# 780-00012-P3_rev3_Sch_M2_Focus_Drive.net
KiCad netlist of a schematic drawn in Altium Designer
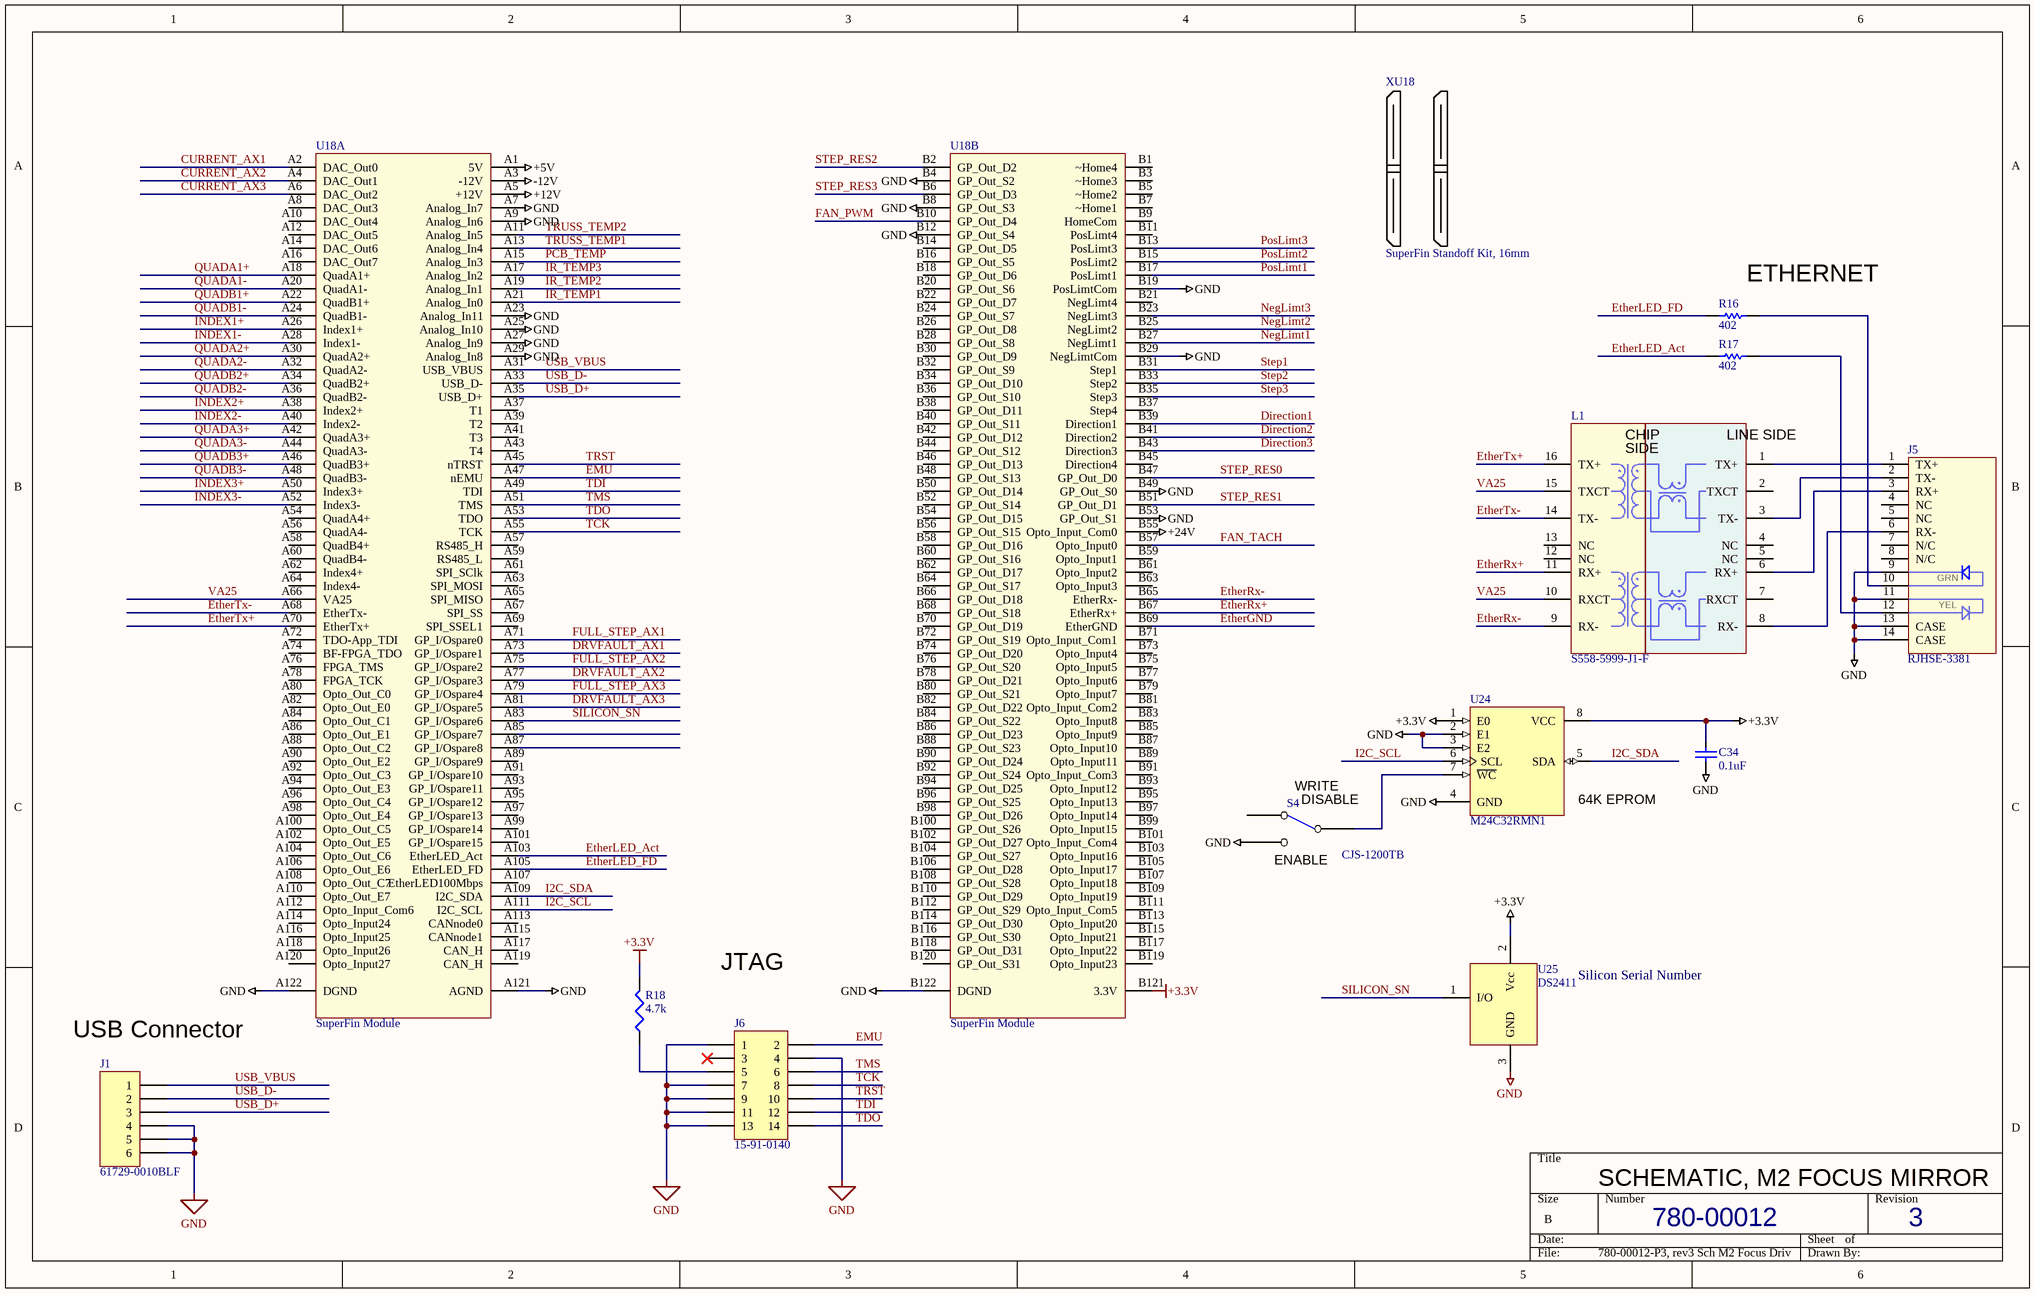
[diagram p0: 780-00012-P3, rev3 Sch M2 Focus Drive.SchDoc]

(export (version "E")
  (design (tool "Eeschema 10.0.6"))
  (components
    (comp (ref "C34")
      (value "0.1uF")
      (footprint "SMD_0805")
      (description "Capacitor")
      (fields (field (name "MANUFACTURER") "AVX") (field (name "Comment") "Cap SMD"))
      (libsource (lib "Richs Schematic Components") (part "Cap SMD"))
    )
    (comp (ref "J1")
      (value "61729-0010BLF")
      (footprint "USB Vertical PCB")
      (description "Header, 6-Pin")
      (fields (field (name "MANUFACTURER") "FCI"))
      (libsource (lib "Miscellaneous Connectors") (part "Header 6"))
    )
    (comp (ref "J5")
      (value "RJHSE-3381")
      (footprint "RJ45, VERT MOUNT, NO MAGNETICS")
      (description "Vertical PC mount, w/o magnetics")
      (libsource (lib "Richs Schematic Components") (part "CONN RJ-45 w/o magnetics"))
    )
    (comp (ref "J6")
      (value "15-91-0140")
      (footprint "HDR2X7")
      (description "Header, 7-Pin, Dual row")
      (fields (field (name "MANUFACTURER") "Molex/Waldom"))
      (libsource (lib "Miscellaneous Connectors") (part "Header 7X2"))
    )
    (comp (ref "L1")
      (value "S558-5999-J1-F")
      (footprint "10/100BT Magetics module")
      (description "10/100BT Magnetics Module")
      (libsource (lib "Richs Schematic Components") (part "Ethernet Magnetics module"))
    )
    (comp (ref "R16")
      (value "402")
      (footprint "SMD_0805")
      (description "Resistor 0805")
      (fields (field (name "MANUFACTURER") "Vishay/Dale") (field (name "Comment") "Res 0805"))
      (libsource (lib "Richs Schematic Components") (part "Res SMD"))
    )
    (comp (ref "R17")
      (value "402")
      (footprint "SMD_0805")
      (description "Resistor 0805")
      (fields (field (name "MANUFACTURER") "Vishay/Dale") (field (name "Comment") "Res 0805"))
      (libsource (lib "Richs Schematic Components") (part "Res SMD"))
    )
    (comp (ref "R18")
      (value "4.7k")
      (footprint "2012[0805]")
      (description "Resistor")
      (fields (field (name "MANUFACTURER") "Dale/Vishay"))
      (libsource (lib "Miscellaneous Devices") (part "Res3"))
    )
    (comp (ref "S4")
      (value "CJS-1200TB")
      (footprint "CAS-120B")
      (fields (field (name "MANUFACTURER") "Copal Electronics"))
      (libsource (lib "JON_1_Library") (part "SW_SPDT_DOUG"))
    )
    (comp (ref "U18")
      (value "SuperFin Module")
      (footprint "SuperFin Footprint")
      (libsource (lib "Richs Schematic Components") (part "SuperFin Module"))
    )
    (comp (ref "U24")
      (value "M24C32RMN1")
      (footprint "SOP8_N")
      (description "32 Kbit Serial I²C Bus EEPROM")
      (libsource (lib "ST Memory EEPROM Serial") (part "M24C32RMN1"))
    )
    (comp (ref "U25")
      (value "DS2411")
      (footprint "SMD_SOT23_3")
      (description "Silicon Serial Number")
      (fields (field (name "MANUFACTURER") "MAXIM"))
      (libsource (lib "Richs Schematic Components") (part "DS2411"))
    )
    (comp (ref "XU18")
      (value "SuperFin Standoff Kit, 16mm")
      (libsource (lib "Richs Schematic Components") (part "SuperFin Standoff Kit, 16mm"))
    )
  )
  (nets
    (net (code "1") (name "+3.3V") (class "Default")
      (node (ref "C34") (pin "2") (pinfunction "2_2") (pintype "passive"))
      (node (ref "R18") (pin "2") (pinfunction "2_2") (pintype "passive"))
      (node (ref "U18") (pin "B121") (pinfunction "3.3V_B121") (pintype "passive"))
      (node (ref "U24") (pin "1") (pinfunction "E0_1") (pintype "input"))
      (node (ref "U24") (pin "8") (pinfunction "VCC_8") (pintype "power_in"))
      (node (ref "U25") (pin "2") (pinfunction "Vcc_2") (pintype "passive"))
    )
    (net (code "2") (name "+5V") (class "Default")
      (node (ref "U18") (pin "A1") (pinfunction "5V_A1") (pintype "passive"))
    )
    (net (code "3") (name "+12V") (class "Default")
      (node (ref "U18") (pin "A5") (pinfunction "+12V_A5") (pintype "passive"))
    )
    (net (code "4") (name "+24V") (class "Default")
      (node (ref "U18") (pin "B55") (pinfunction "Opto_Input_Com0_B55") (pintype "passive"))
    )
    (net (code "5") (name "-12V") (class "Default")
      (node (ref "U18") (pin "A3") (pinfunction "-12V_A3") (pintype "passive"))
    )
    (net (code "6") (name "/CURRENT_AX1") (class "Default")
      (node (ref "U18") (pin "A2") (pinfunction "DAC_Out0_A2") (pintype "passive"))
    )
    (net (code "7") (name "/CURRENT_AX2") (class "Default")
      (node (ref "U18") (pin "A4") (pinfunction "DAC_Out1_A4") (pintype "passive"))
    )
    (net (code "8") (name "/CURRENT_AX3") (class "Default")
      (node (ref "U18") (pin "A6") (pinfunction "DAC_Out2_A6") (pintype "passive"))
    )
    (net (code "9") (name "/DRVFAULT_AX1") (class "Default")
      (node (ref "U18") (pin "A73") (pinfunction "GP_I/Ospare1_A73") (pintype "passive"))
    )
    (net (code "10") (name "/DRVFAULT_AX2") (class "Default")
      (node (ref "U18") (pin "A77") (pinfunction "GP_I/Ospare3_A77") (pintype "passive"))
    )
    (net (code "11") (name "/DRVFAULT_AX3") (class "Default")
      (node (ref "U18") (pin "A81") (pinfunction "GP_I/Ospare5_A81") (pintype "passive"))
    )
    (net (code "12") (name "/Direction1") (class "Default")
      (node (ref "U18") (pin "B39") (pinfunction "Direction1_B39") (pintype "passive"))
    )
    (net (code "13") (name "/Direction2") (class "Default")
      (node (ref "U18") (pin "B41") (pinfunction "Direction2_B41") (pintype "passive"))
    )
    (net (code "14") (name "/Direction3") (class "Default")
      (node (ref "U18") (pin "B43") (pinfunction "Direction3_B43") (pintype "passive"))
    )
    (net (code "15") (name "/EMU") (class "Default")
      (node (ref "J6") (pin "2") (pinfunction "2_2") (pintype "passive"))
      (node (ref "U18") (pin "A47") (pinfunction "nEMU_A47") (pintype "passive"))
    )
    (net (code "16") (name "/EtherGND") (class "Default")
      (node (ref "U18") (pin "B69") (pinfunction "EtherGND_B69") (pintype "passive"))
    )
    (net (code "17") (name "/EtherLED_Act") (class "Default")
      (node (ref "R17") (pin "1") (pinfunction "1_1") (pintype "passive"))
      (node (ref "U18") (pin "A103") (pinfunction "EtherLED_Act_A103") (pintype "passive"))
    )
    (net (code "18") (name "/EtherLED_FD") (class "Default")
      (node (ref "R16") (pin "1") (pinfunction "1_1") (pintype "passive"))
      (node (ref "U18") (pin "A105") (pinfunction "EtherLED_FD_A105") (pintype "passive"))
    )
    (net (code "19") (name "/EtherRx+") (class "Default")
      (node (ref "L1") (pin "11") (pinfunction "RX+_11") (pintype "passive"))
      (node (ref "U18") (pin "B67") (pinfunction "EtherRx+_B67") (pintype "passive"))
    )
    (net (code "20") (name "/EtherRx-") (class "Default")
      (node (ref "L1") (pin "9") (pinfunction "RX-_9") (pintype "passive"))
      (node (ref "U18") (pin "B65") (pinfunction "EtherRx-_B65") (pintype "passive"))
    )
    (net (code "21") (name "/EtherTx+") (class "Default")
      (node (ref "L1") (pin "16") (pinfunction "TX+_16") (pintype "passive"))
      (node (ref "U18") (pin "A70") (pinfunction "EtherTx+_A70") (pintype "passive"))
    )
    (net (code "22") (name "/EtherTx-") (class "Default")
      (node (ref "L1") (pin "14") (pinfunction "TX-_14") (pintype "passive"))
      (node (ref "U18") (pin "A68") (pinfunction "EtherTx-_A68") (pintype "passive"))
    )
    (net (code "23") (name "/FAN_PWM") (class "Default")
      (node (ref "U18") (pin "B10") (pinfunction "GP_Out_D4_B10") (pintype "passive"))
    )
    (net (code "24") (name "/FAN_TACH") (class "Default")
      (node (ref "U18") (pin "B57") (pinfunction "Opto_Input0_B57") (pintype "passive"))
    )
    (net (code "25") (name "/FULL_STEP_AX1") (class "Default")
      (node (ref "U18") (pin "A71") (pinfunction "GP_I/Ospare0_A71") (pintype "passive"))
    )
    (net (code "26") (name "/FULL_STEP_AX2") (class "Default")
      (node (ref "U18") (pin "A75") (pinfunction "GP_I/Ospare2_A75") (pintype "passive"))
    )
    (net (code "27") (name "/FULL_STEP_AX3") (class "Default")
      (node (ref "U18") (pin "A79") (pinfunction "GP_I/Ospare4_A79") (pintype "passive"))
    )
    (net (code "28") (name "/I2C_SCL") (class "Default")
      (node (ref "U18") (pin "A111") (pinfunction "I2C_SCL_A111") (pintype "passive"))
      (node (ref "U24") (pin "6") (pinfunction "SCL_6") (pintype "input"))
    )
    (net (code "29") (name "/I2C_SDA") (class "Default")
      (node (ref "U18") (pin "A109") (pinfunction "I2C_SDA_A109") (pintype "passive"))
      (node (ref "U24") (pin "5") (pinfunction "SDA_5") (pintype "bidirectional"))
    )
    (net (code "30") (name "/INDEX1+") (class "Default")
      (node (ref "U18") (pin "A26") (pinfunction "Index1+_A26") (pintype "passive"))
    )
    (net (code "31") (name "/INDEX1-") (class "Default")
      (node (ref "U18") (pin "A28") (pinfunction "Index1-_A28") (pintype "passive"))
    )
    (net (code "32") (name "/INDEX2+") (class "Default")
      (node (ref "U18") (pin "A38") (pinfunction "Index2+_A38") (pintype "passive"))
    )
    (net (code "33") (name "/INDEX2-") (class "Default")
      (node (ref "U18") (pin "A40") (pinfunction "Index2-_A40") (pintype "passive"))
    )
    (net (code "34") (name "/INDEX3+") (class "Default")
      (node (ref "U18") (pin "A50") (pinfunction "Index3+_A50") (pintype "passive"))
    )
    (net (code "35") (name "/INDEX3-") (class "Default")
      (node (ref "U18") (pin "A52") (pinfunction "Index3-_A52") (pintype "passive"))
    )
    (net (code "36") (name "/IR_TEMP1") (class "Default")
      (node (ref "U18") (pin "A21") (pinfunction "Analog_In0_A21") (pintype "passive"))
    )
    (net (code "37") (name "/IR_TEMP2") (class "Default")
      (node (ref "U18") (pin "A19") (pinfunction "Analog_In1_A19") (pintype "passive"))
    )
    (net (code "38") (name "/IR_TEMP3") (class "Default")
      (node (ref "U18") (pin "A17") (pinfunction "Analog_In2_A17") (pintype "passive"))
    )
    (net (code "39") (name "/NegLimt1") (class "Default")
      (node (ref "U18") (pin "B27") (pinfunction "NegLimt1_B27") (pintype "passive"))
    )
    (net (code "40") (name "/NegLimt2") (class "Default")
      (node (ref "U18") (pin "B25") (pinfunction "NegLimt2_B25") (pintype "passive"))
    )
    (net (code "41") (name "/NegLimt3") (class "Default")
      (node (ref "U18") (pin "B23") (pinfunction "NegLimt3_B23") (pintype "passive"))
    )
    (net (code "42") (name "/PCB_TEMP") (class "Default")
      (node (ref "U18") (pin "A15") (pinfunction "Analog_In3_A15") (pintype "passive"))
    )
    (net (code "43") (name "/PosLimt1") (class "Default")
      (node (ref "U18") (pin "B17") (pinfunction "PosLimt1_B17") (pintype "passive"))
    )
    (net (code "44") (name "/PosLimt2") (class "Default")
      (node (ref "U18") (pin "B15") (pinfunction "PosLimt2_B15") (pintype "passive"))
    )
    (net (code "45") (name "/PosLimt3") (class "Default")
      (node (ref "U18") (pin "B13") (pinfunction "PosLimt3_B13") (pintype "passive"))
    )
    (net (code "46") (name "/QUADA1+") (class "Default")
      (node (ref "U18") (pin "A18") (pinfunction "QuadA1+_A18") (pintype "passive"))
    )
    (net (code "47") (name "/QUADA1-") (class "Default")
      (node (ref "U18") (pin "A20") (pinfunction "QuadA1-_A20") (pintype "passive"))
    )
    (net (code "48") (name "/QUADA2+") (class "Default")
      (node (ref "U18") (pin "A30") (pinfunction "QuadA2+_A30") (pintype "passive"))
    )
    (net (code "49") (name "/QUADA2-") (class "Default")
      (node (ref "U18") (pin "A32") (pinfunction "QuadA2-_A32") (pintype "passive"))
    )
    (net (code "50") (name "/QUADA3+") (class "Default")
      (node (ref "U18") (pin "A42") (pinfunction "QuadA3+_A42") (pintype "passive"))
    )
    (net (code "51") (name "/QUADA3-") (class "Default")
      (node (ref "U18") (pin "A44") (pinfunction "QuadA3-_A44") (pintype "passive"))
    )
    (net (code "52") (name "/QUADB1+") (class "Default")
      (node (ref "U18") (pin "A22") (pinfunction "QuadB1+_A22") (pintype "passive"))
    )
    (net (code "53") (name "/QUADB1-") (class "Default")
      (node (ref "U18") (pin "A24") (pinfunction "QuadB1-_A24") (pintype "passive"))
    )
    (net (code "54") (name "/QUADB2+") (class "Default")
      (node (ref "U18") (pin "A34") (pinfunction "QuadB2+_A34") (pintype "passive"))
    )
    (net (code "55") (name "/QUADB2-") (class "Default")
      (node (ref "U18") (pin "A36") (pinfunction "QuadB2-_A36") (pintype "passive"))
    )
    (net (code "56") (name "/QUADB3+") (class "Default")
      (node (ref "U18") (pin "A46") (pinfunction "QuadB3+_A46") (pintype "passive"))
    )
    (net (code "57") (name "/QUADB3-") (class "Default")
      (node (ref "U18") (pin "A48") (pinfunction "QuadB3-_A48") (pintype "passive"))
    )
    (net (code "58") (name "/SILICON_SN") (class "Default")
      (node (ref "U18") (pin "A83") (pinfunction "GP_I/Ospare6_A83") (pintype "passive"))
      (node (ref "U25") (pin "1") (pinfunction "I/O_1") (pintype "passive"))
    )
    (net (code "59") (name "/STEP_RES0") (class "Default")
      (node (ref "U18") (pin "B47") (pinfunction "GP_Out_D0_B47") (pintype "passive"))
    )
    (net (code "60") (name "/STEP_RES1") (class "Default")
      (node (ref "U18") (pin "B51") (pinfunction "GP_Out_D1_B51") (pintype "passive"))
    )
    (net (code "61") (name "/STEP_RES2") (class "Default")
      (node (ref "U18") (pin "B2") (pinfunction "GP_Out_D2_B2") (pintype "passive"))
    )
    (net (code "62") (name "/STEP_RES3") (class "Default")
      (node (ref "U18") (pin "B6") (pinfunction "GP_Out_D3_B6") (pintype "passive"))
    )
    (net (code "63") (name "/Step1") (class "Default")
      (node (ref "U18") (pin "B31") (pinfunction "Step1_B31") (pintype "passive"))
    )
    (net (code "64") (name "/Step2") (class "Default")
      (node (ref "U18") (pin "B33") (pinfunction "Step2_B33") (pintype "passive"))
    )
    (net (code "65") (name "/Step3") (class "Default")
      (node (ref "U18") (pin "B35") (pinfunction "Step3_B35") (pintype "passive"))
    )
    (net (code "66") (name "/TCK") (class "Default")
      (node (ref "J6") (pin "8") (pinfunction "8_8") (pintype "passive"))
      (node (ref "U18") (pin "A55") (pinfunction "TCK_A55") (pintype "passive"))
    )
    (net (code "67") (name "/TDI") (class "Default")
      (node (ref "J6") (pin "12") (pinfunction "12_12") (pintype "passive"))
      (node (ref "U18") (pin "A49") (pinfunction "TDI_A49") (pintype "passive"))
    )
    (net (code "68") (name "/TDO") (class "Default")
      (node (ref "J6") (pin "14") (pinfunction "14_14") (pintype "passive"))
      (node (ref "U18") (pin "A53") (pinfunction "TDO_A53") (pintype "passive"))
    )
    (net (code "69") (name "/TMS") (class "Default")
      (node (ref "J6") (pin "6") (pinfunction "6_6") (pintype "passive"))
      (node (ref "U18") (pin "A51") (pinfunction "TMS_A51") (pintype "passive"))
    )
    (net (code "70") (name "/TRST") (class "Default")
      (node (ref "J6") (pin "10") (pinfunction "10_10") (pintype "passive"))
      (node (ref "U18") (pin "A45") (pinfunction "nTRST_A45") (pintype "passive"))
    )
    (net (code "71") (name "/TRUSS_TEMP1") (class "Default")
      (node (ref "U18") (pin "A13") (pinfunction "Analog_In4_A13") (pintype "passive"))
    )
    (net (code "72") (name "/TRUSS_TEMP2") (class "Default")
      (node (ref "U18") (pin "A11") (pinfunction "Analog_In5_A11") (pintype "passive"))
    )
    (net (code "73") (name "/USB_D+") (class "Default")
      (node (ref "J1") (pin "3") (pinfunction "3_3") (pintype "passive"))
      (node (ref "U18") (pin "A35") (pinfunction "USB_D+_A35") (pintype "passive"))
    )
    (net (code "74") (name "/USB_D-") (class "Default")
      (node (ref "J1") (pin "2") (pinfunction "2_2") (pintype "passive"))
      (node (ref "U18") (pin "A33") (pinfunction "USB_D-_A33") (pintype "passive"))
    )
    (net (code "75") (name "/USB_VBUS") (class "Default")
      (node (ref "J1") (pin "1") (pinfunction "1_1") (pintype "passive"))
      (node (ref "U18") (pin "A31") (pinfunction "USB_VBUS_A31") (pintype "passive"))
    )
    (net (code "76") (name "/VA25") (class "Default")
      (node (ref "L1") (pin "10") (pinfunction "RXCT_10") (pintype "passive"))
      (node (ref "L1") (pin "15") (pinfunction "TXCT_15") (pintype "passive"))
      (node (ref "U18") (pin "A66") (pinfunction "VA25_A66") (pintype "passive"))
    )
    (net (code "77") (name "GND") (class "Default")
      (node (ref "C34") (pin "1") (pinfunction "1_1") (pintype "passive"))
      (node (ref "J1") (pin "4") (pinfunction "4_4") (pintype "passive"))
      (node (ref "J1") (pin "5") (pinfunction "5_5") (pintype "passive"))
      (node (ref "J1") (pin "6") (pinfunction "6_6") (pintype "passive"))
      (node (ref "J5") (pin "11") (pinfunction "YEL-Cathode_11") (pintype "passive"))
      (node (ref "J5") (pin "13") (pinfunction "CASE_13") (pintype "passive"))
      (node (ref "J5") (pin "14") (pinfunction "CASE_14") (pintype "passive"))
      (node (ref "J5") (pin "9") (pinfunction "GRN-Anode_9") (pintype "passive"))
      (node (ref "J6") (pin "1") (pinfunction "1_1") (pintype "passive"))
      (node (ref "J6") (pin "11") (pinfunction "11_11") (pintype "passive"))
      (node (ref "J6") (pin "13") (pinfunction "13_13") (pintype "passive"))
      (node (ref "J6") (pin "4") (pinfunction "4_4") (pintype "passive"))
      (node (ref "J6") (pin "7") (pinfunction "7_7") (pintype "passive"))
      (node (ref "J6") (pin "9") (pinfunction "9_9") (pintype "passive"))
      (node (ref "S4") (pin "1") (pinfunction "NO_1") (pintype "passive"))
      (node (ref "U18") (pin "A121") (pinfunction "AGND_A121") (pintype "passive"))
      (node (ref "U18") (pin "A122") (pinfunction "DGND_A122") (pintype "passive"))
      (node (ref "U18") (pin "A23") (pinfunction "Analog_In11_A23") (pintype "passive"))
      (node (ref "U18") (pin "A25") (pinfunction "Analog_In10_A25") (pintype "passive"))
      (node (ref "U18") (pin "A27") (pinfunction "Analog_In9_A27") (pintype "passive"))
      (node (ref "U18") (pin "A29") (pinfunction "Analog_In8_A29") (pintype "passive"))
      (node (ref "U18") (pin "A7") (pinfunction "Analog_In7_A7") (pintype "passive"))
      (node (ref "U18") (pin "A9") (pinfunction "Analog_In6_A9") (pintype "passive"))
      (node (ref "U18") (pin "B12") (pinfunction "GP_Out_S4_B12") (pintype "passive"))
      (node (ref "U18") (pin "B122") (pinfunction "DGND_B122") (pintype "passive"))
      (node (ref "U18") (pin "B19") (pinfunction "PosLimtCom_B19") (pintype "passive"))
      (node (ref "U18") (pin "B29") (pinfunction "NegLimtCom_B29") (pintype "passive"))
      (node (ref "U18") (pin "B4") (pinfunction "GP_Out_S2_B4") (pintype "passive"))
      (node (ref "U18") (pin "B49") (pinfunction "GP_Out_S0_B49") (pintype "passive"))
      (node (ref "U18") (pin "B53") (pinfunction "GP_Out_S1_B53") (pintype "passive"))
      (node (ref "U18") (pin "B8") (pinfunction "GP_Out_S3_B8") (pintype "passive"))
      (node (ref "U24") (pin "2") (pinfunction "E1_2") (pintype "input"))
      (node (ref "U24") (pin "3") (pinfunction "E2_3") (pintype "input"))
      (node (ref "U24") (pin "4") (pinfunction "GND_4") (pintype "power_in"))
      (node (ref "U25") (pin "3") (pinfunction "GND_3") (pintype "passive"))
    )
    (net (code "78") (name "Net-(J5-GRN-Cathode)") (class "Default")
      (node (ref "J5") (pin "10") (pinfunction "GRN-Cathode_10") (pintype "passive"))
      (node (ref "R16") (pin "2") (pinfunction "2_2") (pintype "passive"))
    )
    (net (code "79") (name "Net-(J5-RX+)") (class "Default")
      (node (ref "J5") (pin "3") (pinfunction "RX+_3") (pintype "passive"))
      (node (ref "L1") (pin "6") (pinfunction "RX+_6") (pintype "passive"))
    )
    (net (code "80") (name "Net-(J5-RX-)") (class "Default")
      (node (ref "J5") (pin "6") (pinfunction "RX-_6") (pintype "passive"))
      (node (ref "L1") (pin "8") (pinfunction "RX-_8") (pintype "passive"))
    )
    (net (code "81") (name "Net-(J5-TX+)") (class "Default")
      (node (ref "J5") (pin "1") (pinfunction "TX+_1") (pintype "passive"))
      (node (ref "L1") (pin "1") (pinfunction "TX+_1") (pintype "passive"))
    )
    (net (code "82") (name "Net-(J5-TX-)") (class "Default")
      (node (ref "J5") (pin "2") (pinfunction "TX-_2") (pintype "passive"))
      (node (ref "L1") (pin "3") (pinfunction "TX-_3") (pintype "passive"))
    )
    (net (code "83") (name "Net-(J5-YEL-Anode)") (class "Default")
      (node (ref "J5") (pin "12") (pinfunction "YEL-Anode_12") (pintype "passive"))
      (node (ref "R17") (pin "2") (pinfunction "2_2") (pintype "passive"))
    )
    (net (code "84") (name "Net-(J6-Pad5)") (class "Default")
      (node (ref "J6") (pin "5") (pinfunction "5_5") (pintype "passive"))
      (node (ref "R18") (pin "1") (pinfunction "1_1") (pintype "passive"))
    )
    (net (code "85") (name "Net-(S4-COM)") (class "Default")
      (node (ref "S4") (pin "2") (pinfunction "COM_2") (pintype "passive"))
      (node (ref "U24") (pin "7") (pinfunction "~{WC}_7") (pintype "input"))
    )
    (net (code "86") (name "unconnected-(J5-NC-Pad4)") (class "Default")
      (node (ref "J5") (pin "4") (pinfunction "NC_4") (pintype "passive"))
    )
    (net (code "87") (name "unconnected-(J5-NC-Pad5)") (class "Default")
      (node (ref "J5") (pin "5") (pinfunction "NC_5") (pintype "passive"))
    )
    (net (code "88") (name "unconnected-(J5-N{slash}C-Pad7)") (class "Default")
      (node (ref "J5") (pin "7") (pinfunction "N/C_7") (pintype "passive"))
    )
    (net (code "89") (name "unconnected-(J5-N{slash}C-Pad8)") (class "Default")
      (node (ref "J5") (pin "8") (pinfunction "N/C_8") (pintype "passive"))
    )
    (net (code "90") (name "unconnected-(J6-Pad3)") (class "Default")
      (node (ref "J6") (pin "3") (pinfunction "3_3") (pintype "passive+no_connect"))
    )
    (net (code "91") (name "unconnected-(L1-NC-Pad4)") (class "Default")
      (node (ref "L1") (pin "4") (pinfunction "NC_4") (pintype "passive"))
    )
    (net (code "92") (name "unconnected-(L1-NC-Pad5)") (class "Default")
      (node (ref "L1") (pin "5") (pinfunction "NC_5") (pintype "passive"))
    )
    (net (code "93") (name "unconnected-(L1-NC-Pad12)") (class "Default")
      (node (ref "L1") (pin "12") (pinfunction "NC_12") (pintype "passive"))
    )
    (net (code "94") (name "unconnected-(L1-NC-Pad13)") (class "Default")
      (node (ref "L1") (pin "13") (pinfunction "NC_13") (pintype "passive"))
    )
    (net (code "95") (name "unconnected-(L1-RXCT-Pad7)") (class "Default")
      (node (ref "L1") (pin "7") (pinfunction "RXCT_7") (pintype "passive"))
    )
    (net (code "96") (name "unconnected-(L1-TXCT-Pad2)") (class "Default")
      (node (ref "L1") (pin "2") (pinfunction "TXCT_2") (pintype "passive"))
    )
    (net (code "97") (name "unconnected-(S4-NC-Pad3)") (class "Default")
      (node (ref "S4") (pin "3") (pinfunction "NC_3") (pintype "passive"))
    )
    (net (code "98") (name "unconnected-(U18A-BF-FPGA_TDO-PadA74)") (class "Default")
      (node (ref "U18") (pin "A74") (pinfunction "BF-FPGA_TDO_A74") (pintype "passive"))
    )
    (net (code "99") (name "unconnected-(U18A-CAN_H-PadA117)") (class "Default")
      (node (ref "U18") (pin "A117") (pinfunction "CAN_H_A117") (pintype "passive"))
    )
    (net (code "100") (name "unconnected-(U18A-CAN_H-PadA119)") (class "Default")
      (node (ref "U18") (pin "A119") (pinfunction "CAN_H_A119") (pintype "passive"))
    )
    (net (code "101") (name "unconnected-(U18A-CANnode0-PadA113)") (class "Default")
      (node (ref "U18") (pin "A113") (pinfunction "CANnode0_A113") (pintype "passive"))
    )
    (net (code "102") (name "unconnected-(U18A-CANnode1-PadA115)") (class "Default")
      (node (ref "U18") (pin "A115") (pinfunction "CANnode1_A115") (pintype "passive"))
    )
    (net (code "103") (name "unconnected-(U18A-DAC_Out3-PadA8)") (class "Default")
      (node (ref "U18") (pin "A8") (pinfunction "DAC_Out3_A8") (pintype "passive"))
    )
    (net (code "104") (name "unconnected-(U18A-DAC_Out4-PadA10)") (class "Default")
      (node (ref "U18") (pin "A10") (pinfunction "DAC_Out4_A10") (pintype "passive"))
    )
    (net (code "105") (name "unconnected-(U18A-DAC_Out5-PadA12)") (class "Default")
      (node (ref "U18") (pin "A12") (pinfunction "DAC_Out5_A12") (pintype "passive"))
    )
    (net (code "106") (name "unconnected-(U18A-DAC_Out6-PadA14)") (class "Default")
      (node (ref "U18") (pin "A14") (pinfunction "DAC_Out6_A14") (pintype "passive"))
    )
    (net (code "107") (name "unconnected-(U18A-DAC_Out7-PadA16)") (class "Default")
      (node (ref "U18") (pin "A16") (pinfunction "DAC_Out7_A16") (pintype "passive"))
    )
    (net (code "108") (name "unconnected-(U18A-EtherLED100Mbps-PadA107)") (class "Default")
      (node (ref "U18") (pin "A107") (pinfunction "EtherLED100Mbps_A107") (pintype "passive"))
    )
    (net (code "109") (name "unconnected-(U18A-FPGA_TCK-PadA78)") (class "Default")
      (node (ref "U18") (pin "A78") (pinfunction "FPGA_TCK_A78") (pintype "passive"))
    )
    (net (code "110") (name "unconnected-(U18A-FPGA_TMS-PadA76)") (class "Default")
      (node (ref "U18") (pin "A76") (pinfunction "FPGA_TMS_A76") (pintype "passive"))
    )
    (net (code "111") (name "unconnected-(U18A-GP_I{slash}Ospare7-PadA85)") (class "Default")
      (node (ref "U18") (pin "A85") (pinfunction "GP_I/Ospare7_A85") (pintype "passive"))
    )
    (net (code "112") (name "unconnected-(U18A-GP_I{slash}Ospare8-PadA87)") (class "Default")
      (node (ref "U18") (pin "A87") (pinfunction "GP_I/Ospare8_A87") (pintype "passive"))
    )
    (net (code "113") (name "unconnected-(U18A-GP_I{slash}Ospare9-PadA89)") (class "Default")
      (node (ref "U18") (pin "A89") (pinfunction "GP_I/Ospare9_A89") (pintype "passive"))
    )
    (net (code "114") (name "unconnected-(U18A-GP_I{slash}Ospare10-PadA91)") (class "Default")
      (node (ref "U18") (pin "A91") (pinfunction "GP_I/Ospare10_A91") (pintype "passive"))
    )
    (net (code "115") (name "unconnected-(U18A-GP_I{slash}Ospare11-PadA93)") (class "Default")
      (node (ref "U18") (pin "A93") (pinfunction "GP_I/Ospare11_A93") (pintype "passive"))
    )
    (net (code "116") (name "unconnected-(U18A-GP_I{slash}Ospare12-PadA95)") (class "Default")
      (node (ref "U18") (pin "A95") (pinfunction "GP_I/Ospare12_A95") (pintype "passive"))
    )
    (net (code "117") (name "unconnected-(U18A-GP_I{slash}Ospare13-PadA97)") (class "Default")
      (node (ref "U18") (pin "A97") (pinfunction "GP_I/Ospare13_A97") (pintype "passive"))
    )
    (net (code "118") (name "unconnected-(U18A-GP_I{slash}Ospare14-PadA99)") (class "Default")
      (node (ref "U18") (pin "A99") (pinfunction "GP_I/Ospare14_A99") (pintype "passive"))
    )
    (net (code "119") (name "unconnected-(U18A-GP_I{slash}Ospare15-PadA101)") (class "Default")
      (node (ref "U18") (pin "A101") (pinfunction "GP_I/Ospare15_A101") (pintype "passive"))
    )
    (net (code "120") (name "unconnected-(U18A-Index4+-PadA62)") (class "Default")
      (node (ref "U18") (pin "A62") (pinfunction "Index4+_A62") (pintype "passive"))
    )
    (net (code "121") (name "unconnected-(U18A-Index4--PadA64)") (class "Default")
      (node (ref "U18") (pin "A64") (pinfunction "Index4-_A64") (pintype "passive"))
    )
    (net (code "122") (name "unconnected-(U18A-Opto_Input24-PadA114)") (class "Default")
      (node (ref "U18") (pin "A114") (pinfunction "Opto_Input24_A114") (pintype "passive"))
    )
    (net (code "123") (name "unconnected-(U18A-Opto_Input25-PadA116)") (class "Default")
      (node (ref "U18") (pin "A116") (pinfunction "Opto_Input25_A116") (pintype "passive"))
    )
    (net (code "124") (name "unconnected-(U18A-Opto_Input26-PadA118)") (class "Default")
      (node (ref "U18") (pin "A118") (pinfunction "Opto_Input26_A118") (pintype "passive"))
    )
    (net (code "125") (name "unconnected-(U18A-Opto_Input27-PadA120)") (class "Default")
      (node (ref "U18") (pin "A120") (pinfunction "Opto_Input27_A120") (pintype "passive"))
    )
    (net (code "126") (name "unconnected-(U18A-Opto_Input_Com6-PadA112)") (class "Default")
      (node (ref "U18") (pin "A112") (pinfunction "Opto_Input_Com6_A112") (pintype "passive"))
    )
    (net (code "127") (name "unconnected-(U18A-Opto_Out_C0-PadA80)") (class "Default")
      (node (ref "U18") (pin "A80") (pinfunction "Opto_Out_C0_A80") (pintype "passive"))
    )
    (net (code "128") (name "unconnected-(U18A-Opto_Out_C1-PadA84)") (class "Default")
      (node (ref "U18") (pin "A84") (pinfunction "Opto_Out_C1_A84") (pintype "passive"))
    )
    (net (code "129") (name "unconnected-(U18A-Opto_Out_C2-PadA88)") (class "Default")
      (node (ref "U18") (pin "A88") (pinfunction "Opto_Out_C2_A88") (pintype "passive"))
    )
    (net (code "130") (name "unconnected-(U18A-Opto_Out_C3-PadA92)") (class "Default")
      (node (ref "U18") (pin "A92") (pinfunction "Opto_Out_C3_A92") (pintype "passive"))
    )
    (net (code "131") (name "unconnected-(U18A-Opto_Out_C4-PadA96)") (class "Default")
      (node (ref "U18") (pin "A96") (pinfunction "Opto_Out_C4_A96") (pintype "passive"))
    )
    (net (code "132") (name "unconnected-(U18A-Opto_Out_C5-PadA100)") (class "Default")
      (node (ref "U18") (pin "A100") (pinfunction "Opto_Out_C5_A100") (pintype "passive"))
    )
    (net (code "133") (name "unconnected-(U18A-Opto_Out_C6-PadA104)") (class "Default")
      (node (ref "U18") (pin "A104") (pinfunction "Opto_Out_C6_A104") (pintype "passive"))
    )
    (net (code "134") (name "unconnected-(U18A-Opto_Out_C7-PadA108)") (class "Default")
      (node (ref "U18") (pin "A108") (pinfunction "Opto_Out_C7_A108") (pintype "passive"))
    )
    (net (code "135") (name "unconnected-(U18A-Opto_Out_E0-PadA82)") (class "Default")
      (node (ref "U18") (pin "A82") (pinfunction "Opto_Out_E0_A82") (pintype "passive"))
    )
    (net (code "136") (name "unconnected-(U18A-Opto_Out_E1-PadA86)") (class "Default")
      (node (ref "U18") (pin "A86") (pinfunction "Opto_Out_E1_A86") (pintype "passive"))
    )
    (net (code "137") (name "unconnected-(U18A-Opto_Out_E2-PadA90)") (class "Default")
      (node (ref "U18") (pin "A90") (pinfunction "Opto_Out_E2_A90") (pintype "passive"))
    )
    (net (code "138") (name "unconnected-(U18A-Opto_Out_E3-PadA94)") (class "Default")
      (node (ref "U18") (pin "A94") (pinfunction "Opto_Out_E3_A94") (pintype "passive"))
    )
    (net (code "139") (name "unconnected-(U18A-Opto_Out_E4-PadA98)") (class "Default")
      (node (ref "U18") (pin "A98") (pinfunction "Opto_Out_E4_A98") (pintype "passive"))
    )
    (net (code "140") (name "unconnected-(U18A-Opto_Out_E5-PadA102)") (class "Default")
      (node (ref "U18") (pin "A102") (pinfunction "Opto_Out_E5_A102") (pintype "passive"))
    )
    (net (code "141") (name "unconnected-(U18A-Opto_Out_E6-PadA106)") (class "Default")
      (node (ref "U18") (pin "A106") (pinfunction "Opto_Out_E6_A106") (pintype "passive"))
    )
    (net (code "142") (name "unconnected-(U18A-Opto_Out_E7-PadA110)") (class "Default")
      (node (ref "U18") (pin "A110") (pinfunction "Opto_Out_E7_A110") (pintype "passive"))
    )
    (net (code "143") (name "unconnected-(U18A-QuadA4+-PadA54)") (class "Default")
      (node (ref "U18") (pin "A54") (pinfunction "QuadA4+_A54") (pintype "passive"))
    )
    (net (code "144") (name "unconnected-(U18A-QuadA4--PadA56)") (class "Default")
      (node (ref "U18") (pin "A56") (pinfunction "QuadA4-_A56") (pintype "passive"))
    )
    (net (code "145") (name "unconnected-(U18A-QuadB4+-PadA58)") (class "Default")
      (node (ref "U18") (pin "A58") (pinfunction "QuadB4+_A58") (pintype "passive"))
    )
    (net (code "146") (name "unconnected-(U18A-QuadB4--PadA60)") (class "Default")
      (node (ref "U18") (pin "A60") (pinfunction "QuadB4-_A60") (pintype "passive"))
    )
    (net (code "147") (name "unconnected-(U18A-RS485_H-PadA57)") (class "Default")
      (node (ref "U18") (pin "A57") (pinfunction "RS485_H_A57") (pintype "passive"))
    )
    (net (code "148") (name "unconnected-(U18A-RS485_L-PadA59)") (class "Default")
      (node (ref "U18") (pin "A59") (pinfunction "RS485_L_A59") (pintype "passive"))
    )
    (net (code "149") (name "unconnected-(U18A-SPI_MISO-PadA65)") (class "Default")
      (node (ref "U18") (pin "A65") (pinfunction "SPI_MISO_A65") (pintype "passive"))
    )
    (net (code "150") (name "unconnected-(U18A-SPI_MOSI-PadA63)") (class "Default")
      (node (ref "U18") (pin "A63") (pinfunction "SPI_MOSI_A63") (pintype "passive"))
    )
    (net (code "151") (name "unconnected-(U18A-SPI_SClk-PadA61)") (class "Default")
      (node (ref "U18") (pin "A61") (pinfunction "SPI_SClk_A61") (pintype "passive"))
    )
    (net (code "152") (name "unconnected-(U18A-SPI_SS-PadA67)") (class "Default")
      (node (ref "U18") (pin "A67") (pinfunction "SPI_SS_A67") (pintype "passive"))
    )
    (net (code "153") (name "unconnected-(U18A-SPI_SSEL1-PadA69)") (class "Default")
      (node (ref "U18") (pin "A69") (pinfunction "SPI_SSEL1_A69") (pintype "passive"))
    )
    (net (code "154") (name "unconnected-(U18A-T1-PadA37)") (class "Default")
      (node (ref "U18") (pin "A37") (pinfunction "T1_A37") (pintype "passive"))
    )
    (net (code "155") (name "unconnected-(U18A-T2-PadA39)") (class "Default")
      (node (ref "U18") (pin "A39") (pinfunction "T2_A39") (pintype "passive"))
    )
    (net (code "156") (name "unconnected-(U18A-T3-PadA41)") (class "Default")
      (node (ref "U18") (pin "A41") (pinfunction "T3_A41") (pintype "passive"))
    )
    (net (code "157") (name "unconnected-(U18A-T4-PadA43)") (class "Default")
      (node (ref "U18") (pin "A43") (pinfunction "T4_A43") (pintype "passive"))
    )
    (net (code "158") (name "unconnected-(U18A-TDO-App_TDI-PadA72)") (class "Default")
      (node (ref "U18") (pin "A72") (pinfunction "TDO-App_TDI_A72") (pintype "passive"))
    )
    (net (code "159") (name "unconnected-(U18B-Direction4-PadB45)") (class "Default")
      (node (ref "U18") (pin "B45") (pinfunction "Direction4_B45") (pintype "passive"))
    )
    (net (code "160") (name "unconnected-(U18B-GP_Out_D5-PadB14)") (class "Default")
      (node (ref "U18") (pin "B14") (pinfunction "GP_Out_D5_B14") (pintype "passive"))
    )
    (net (code "161") (name "unconnected-(U18B-GP_Out_D6-PadB18)") (class "Default")
      (node (ref "U18") (pin "B18") (pinfunction "GP_Out_D6_B18") (pintype "passive"))
    )
    (net (code "162") (name "unconnected-(U18B-GP_Out_D7-PadB22)") (class "Default")
      (node (ref "U18") (pin "B22") (pinfunction "GP_Out_D7_B22") (pintype "passive"))
    )
    (net (code "163") (name "unconnected-(U18B-GP_Out_D8-PadB26)") (class "Default")
      (node (ref "U18") (pin "B26") (pinfunction "GP_Out_D8_B26") (pintype "passive"))
    )
    (net (code "164") (name "unconnected-(U18B-GP_Out_D9-PadB30)") (class "Default")
      (node (ref "U18") (pin "B30") (pinfunction "GP_Out_D9_B30") (pintype "passive"))
    )
    (net (code "165") (name "unconnected-(U18B-GP_Out_D10-PadB34)") (class "Default")
      (node (ref "U18") (pin "B34") (pinfunction "GP_Out_D10_B34") (pintype "passive"))
    )
    (net (code "166") (name "unconnected-(U18B-GP_Out_D11-PadB38)") (class "Default")
      (node (ref "U18") (pin "B38") (pinfunction "GP_Out_D11_B38") (pintype "passive"))
    )
    (net (code "167") (name "unconnected-(U18B-GP_Out_D12-PadB42)") (class "Default")
      (node (ref "U18") (pin "B42") (pinfunction "GP_Out_D12_B42") (pintype "passive"))
    )
    (net (code "168") (name "unconnected-(U18B-GP_Out_D13-PadB46)") (class "Default")
      (node (ref "U18") (pin "B46") (pinfunction "GP_Out_D13_B46") (pintype "passive"))
    )
    (net (code "169") (name "unconnected-(U18B-GP_Out_D14-PadB50)") (class "Default")
      (node (ref "U18") (pin "B50") (pinfunction "GP_Out_D14_B50") (pintype "passive"))
    )
    (net (code "170") (name "unconnected-(U18B-GP_Out_D15-PadB54)") (class "Default")
      (node (ref "U18") (pin "B54") (pinfunction "GP_Out_D15_B54") (pintype "passive"))
    )
    (net (code "171") (name "unconnected-(U18B-GP_Out_D16-PadB58)") (class "Default")
      (node (ref "U18") (pin "B58") (pinfunction "GP_Out_D16_B58") (pintype "passive"))
    )
    (net (code "172") (name "unconnected-(U18B-GP_Out_D17-PadB62)") (class "Default")
      (node (ref "U18") (pin "B62") (pinfunction "GP_Out_D17_B62") (pintype "passive"))
    )
    (net (code "173") (name "unconnected-(U18B-GP_Out_D18-PadB66)") (class "Default")
      (node (ref "U18") (pin "B66") (pinfunction "GP_Out_D18_B66") (pintype "passive"))
    )
    (net (code "174") (name "unconnected-(U18B-GP_Out_D19-PadB70)") (class "Default")
      (node (ref "U18") (pin "B70") (pinfunction "GP_Out_D19_B70") (pintype "passive"))
    )
    (net (code "175") (name "unconnected-(U18B-GP_Out_D20-PadB74)") (class "Default")
      (node (ref "U18") (pin "B74") (pinfunction "GP_Out_D20_B74") (pintype "passive"))
    )
    (net (code "176") (name "unconnected-(U18B-GP_Out_D21-PadB78)") (class "Default")
      (node (ref "U18") (pin "B78") (pinfunction "GP_Out_D21_B78") (pintype "passive"))
    )
    (net (code "177") (name "unconnected-(U18B-GP_Out_D22-PadB82)") (class "Default")
      (node (ref "U18") (pin "B82") (pinfunction "GP_Out_D22_B82") (pintype "passive"))
    )
    (net (code "178") (name "unconnected-(U18B-GP_Out_D23-PadB86)") (class "Default")
      (node (ref "U18") (pin "B86") (pinfunction "GP_Out_D23_B86") (pintype "passive"))
    )
    (net (code "179") (name "unconnected-(U18B-GP_Out_D24-PadB90)") (class "Default")
      (node (ref "U18") (pin "B90") (pinfunction "GP_Out_D24_B90") (pintype "passive"))
    )
    (net (code "180") (name "unconnected-(U18B-GP_Out_D25-PadB94)") (class "Default")
      (node (ref "U18") (pin "B94") (pinfunction "GP_Out_D25_B94") (pintype "passive"))
    )
    (net (code "181") (name "unconnected-(U18B-GP_Out_D26-PadB98)") (class "Default")
      (node (ref "U18") (pin "B98") (pinfunction "GP_Out_D26_B98") (pintype "passive"))
    )
    (net (code "182") (name "unconnected-(U18B-GP_Out_D27-PadB102)") (class "Default")
      (node (ref "U18") (pin "B102") (pinfunction "GP_Out_D27_B102") (pintype "passive"))
    )
    (net (code "183") (name "unconnected-(U18B-GP_Out_D28-PadB106)") (class "Default")
      (node (ref "U18") (pin "B106") (pinfunction "GP_Out_D28_B106") (pintype "passive"))
    )
    (net (code "184") (name "unconnected-(U18B-GP_Out_D29-PadB110)") (class "Default")
      (node (ref "U18") (pin "B110") (pinfunction "GP_Out_D29_B110") (pintype "passive"))
    )
    (net (code "185") (name "unconnected-(U18B-GP_Out_D30-PadB114)") (class "Default")
      (node (ref "U18") (pin "B114") (pinfunction "GP_Out_D30_B114") (pintype "passive"))
    )
    (net (code "186") (name "unconnected-(U18B-GP_Out_D31-PadB118)") (class "Default")
      (node (ref "U18") (pin "B118") (pinfunction "GP_Out_D31_B118") (pintype "passive"))
    )
    (net (code "187") (name "unconnected-(U18B-GP_Out_S5-PadB16)") (class "Default")
      (node (ref "U18") (pin "B16") (pinfunction "GP_Out_S5_B16") (pintype "passive"))
    )
    (net (code "188") (name "unconnected-(U18B-GP_Out_S6-PadB20)") (class "Default")
      (node (ref "U18") (pin "B20") (pinfunction "GP_Out_S6_B20") (pintype "passive"))
    )
    (net (code "189") (name "unconnected-(U18B-GP_Out_S7-PadB24)") (class "Default")
      (node (ref "U18") (pin "B24") (pinfunction "GP_Out_S7_B24") (pintype "passive"))
    )
    (net (code "190") (name "unconnected-(U18B-GP_Out_S8-PadB28)") (class "Default")
      (node (ref "U18") (pin "B28") (pinfunction "GP_Out_S8_B28") (pintype "passive"))
    )
    (net (code "191") (name "unconnected-(U18B-GP_Out_S9-PadB32)") (class "Default")
      (node (ref "U18") (pin "B32") (pinfunction "GP_Out_S9_B32") (pintype "passive"))
    )
    (net (code "192") (name "unconnected-(U18B-GP_Out_S10-PadB36)") (class "Default")
      (node (ref "U18") (pin "B36") (pinfunction "GP_Out_S10_B36") (pintype "passive"))
    )
    (net (code "193") (name "unconnected-(U18B-GP_Out_S11-PadB40)") (class "Default")
      (node (ref "U18") (pin "B40") (pinfunction "GP_Out_S11_B40") (pintype "passive"))
    )
    (net (code "194") (name "unconnected-(U18B-GP_Out_S12-PadB44)") (class "Default")
      (node (ref "U18") (pin "B44") (pinfunction "GP_Out_S12_B44") (pintype "passive"))
    )
    (net (code "195") (name "unconnected-(U18B-GP_Out_S13-PadB48)") (class "Default")
      (node (ref "U18") (pin "B48") (pinfunction "GP_Out_S13_B48") (pintype "passive"))
    )
    (net (code "196") (name "unconnected-(U18B-GP_Out_S14-PadB52)") (class "Default")
      (node (ref "U18") (pin "B52") (pinfunction "GP_Out_S14_B52") (pintype "passive"))
    )
    (net (code "197") (name "unconnected-(U18B-GP_Out_S15-PadB56)") (class "Default")
      (node (ref "U18") (pin "B56") (pinfunction "GP_Out_S15_B56") (pintype "passive"))
    )
    (net (code "198") (name "unconnected-(U18B-GP_Out_S16-PadB60)") (class "Default")
      (node (ref "U18") (pin "B60") (pinfunction "GP_Out_S16_B60") (pintype "passive"))
    )
    (net (code "199") (name "unconnected-(U18B-GP_Out_S17-PadB64)") (class "Default")
      (node (ref "U18") (pin "B64") (pinfunction "GP_Out_S17_B64") (pintype "passive"))
    )
    (net (code "200") (name "unconnected-(U18B-GP_Out_S18-PadB68)") (class "Default")
      (node (ref "U18") (pin "B68") (pinfunction "GP_Out_S18_B68") (pintype "passive"))
    )
    (net (code "201") (name "unconnected-(U18B-GP_Out_S19-PadB72)") (class "Default")
      (node (ref "U18") (pin "B72") (pinfunction "GP_Out_S19_B72") (pintype "passive"))
    )
    (net (code "202") (name "unconnected-(U18B-GP_Out_S20-PadB76)") (class "Default")
      (node (ref "U18") (pin "B76") (pinfunction "GP_Out_S20_B76") (pintype "passive"))
    )
    (net (code "203") (name "unconnected-(U18B-GP_Out_S21-PadB80)") (class "Default")
      (node (ref "U18") (pin "B80") (pinfunction "GP_Out_S21_B80") (pintype "passive"))
    )
    (net (code "204") (name "unconnected-(U18B-GP_Out_S22-PadB84)") (class "Default")
      (node (ref "U18") (pin "B84") (pinfunction "GP_Out_S22_B84") (pintype "passive"))
    )
    (net (code "205") (name "unconnected-(U18B-GP_Out_S23-PadB88)") (class "Default")
      (node (ref "U18") (pin "B88") (pinfunction "GP_Out_S23_B88") (pintype "passive"))
    )
    (net (code "206") (name "unconnected-(U18B-GP_Out_S24-PadB92)") (class "Default")
      (node (ref "U18") (pin "B92") (pinfunction "GP_Out_S24_B92") (pintype "passive"))
    )
    (net (code "207") (name "unconnected-(U18B-GP_Out_S25-PadB96)") (class "Default")
      (node (ref "U18") (pin "B96") (pinfunction "GP_Out_S25_B96") (pintype "passive"))
    )
    (net (code "208") (name "unconnected-(U18B-GP_Out_S26-PadB100)") (class "Default")
      (node (ref "U18") (pin "B100") (pinfunction "GP_Out_S26_B100") (pintype "passive"))
    )
    (net (code "209") (name "unconnected-(U18B-GP_Out_S27-PadB104)") (class "Default")
      (node (ref "U18") (pin "B104") (pinfunction "GP_Out_S27_B104") (pintype "passive"))
    )
    (net (code "210") (name "unconnected-(U18B-GP_Out_S28-PadB108)") (class "Default")
      (node (ref "U18") (pin "B108") (pinfunction "GP_Out_S28_B108") (pintype "passive"))
    )
    (net (code "211") (name "unconnected-(U18B-GP_Out_S29-PadB112)") (class "Default")
      (node (ref "U18") (pin "B112") (pinfunction "GP_Out_S29_B112") (pintype "passive"))
    )
    (net (code "212") (name "unconnected-(U18B-GP_Out_S30-PadB116)") (class "Default")
      (node (ref "U18") (pin "B116") (pinfunction "GP_Out_S30_B116") (pintype "passive"))
    )
    (net (code "213") (name "unconnected-(U18B-GP_Out_S31-PadB120)") (class "Default")
      (node (ref "U18") (pin "B120") (pinfunction "GP_Out_S31_B120") (pintype "passive"))
    )
    (net (code "214") (name "unconnected-(U18B-HomeCom-PadB9)") (class "Default")
      (node (ref "U18") (pin "B9") (pinfunction "HomeCom_B9") (pintype "passive"))
    )
    (net (code "215") (name "unconnected-(U18B-NegLimt4-PadB21)") (class "Default")
      (node (ref "U18") (pin "B21") (pinfunction "NegLimt4_B21") (pintype "passive"))
    )
    (net (code "216") (name "unconnected-(U18B-Opto_Input1-PadB59)") (class "Default")
      (node (ref "U18") (pin "B59") (pinfunction "Opto_Input1_B59") (pintype "passive"))
    )
    (net (code "217") (name "unconnected-(U18B-Opto_Input2-PadB61)") (class "Default")
      (node (ref "U18") (pin "B61") (pinfunction "Opto_Input2_B61") (pintype "passive"))
    )
    (net (code "218") (name "unconnected-(U18B-Opto_Input3-PadB63)") (class "Default")
      (node (ref "U18") (pin "B63") (pinfunction "Opto_Input3_B63") (pintype "passive"))
    )
    (net (code "219") (name "unconnected-(U18B-Opto_Input4-PadB73)") (class "Default")
      (node (ref "U18") (pin "B73") (pinfunction "Opto_Input4_B73") (pintype "passive"))
    )
    (net (code "220") (name "unconnected-(U18B-Opto_Input5-PadB75)") (class "Default")
      (node (ref "U18") (pin "B75") (pinfunction "Opto_Input5_B75") (pintype "passive"))
    )
    (net (code "221") (name "unconnected-(U18B-Opto_Input6-PadB77)") (class "Default")
      (node (ref "U18") (pin "B77") (pinfunction "Opto_Input6_B77") (pintype "passive"))
    )
    (net (code "222") (name "unconnected-(U18B-Opto_Input7-PadB79)") (class "Default")
      (node (ref "U18") (pin "B79") (pinfunction "Opto_Input7_B79") (pintype "passive"))
    )
    (net (code "223") (name "unconnected-(U18B-Opto_Input8-PadB83)") (class "Default")
      (node (ref "U18") (pin "B83") (pinfunction "Opto_Input8_B83") (pintype "passive"))
    )
    (net (code "224") (name "unconnected-(U18B-Opto_Input9-PadB85)") (class "Default")
      (node (ref "U18") (pin "B85") (pinfunction "Opto_Input9_B85") (pintype "passive"))
    )
    (net (code "225") (name "unconnected-(U18B-Opto_Input10-PadB87)") (class "Default")
      (node (ref "U18") (pin "B87") (pinfunction "Opto_Input10_B87") (pintype "passive"))
    )
    (net (code "226") (name "unconnected-(U18B-Opto_Input11-PadB89)") (class "Default")
      (node (ref "U18") (pin "B89") (pinfunction "Opto_Input11_B89") (pintype "passive"))
    )
    (net (code "227") (name "unconnected-(U18B-Opto_Input12-PadB93)") (class "Default")
      (node (ref "U18") (pin "B93") (pinfunction "Opto_Input12_B93") (pintype "passive"))
    )
    (net (code "228") (name "unconnected-(U18B-Opto_Input13-PadB95)") (class "Default")
      (node (ref "U18") (pin "B95") (pinfunction "Opto_Input13_B95") (pintype "passive"))
    )
    (net (code "229") (name "unconnected-(U18B-Opto_Input14-PadB97)") (class "Default")
      (node (ref "U18") (pin "B97") (pinfunction "Opto_Input14_B97") (pintype "passive"))
    )
    (net (code "230") (name "unconnected-(U18B-Opto_Input15-PadB99)") (class "Default")
      (node (ref "U18") (pin "B99") (pinfunction "Opto_Input15_B99") (pintype "passive"))
    )
    (net (code "231") (name "unconnected-(U18B-Opto_Input16-PadB103)") (class "Default")
      (node (ref "U18") (pin "B103") (pinfunction "Opto_Input16_B103") (pintype "passive"))
    )
    (net (code "232") (name "unconnected-(U18B-Opto_Input17-PadB105)") (class "Default")
      (node (ref "U18") (pin "B105") (pinfunction "Opto_Input17_B105") (pintype "passive"))
    )
    (net (code "233") (name "unconnected-(U18B-Opto_Input18-PadB107)") (class "Default")
      (node (ref "U18") (pin "B107") (pinfunction "Opto_Input18_B107") (pintype "passive"))
    )
    (net (code "234") (name "unconnected-(U18B-Opto_Input19-PadB109)") (class "Default")
      (node (ref "U18") (pin "B109") (pinfunction "Opto_Input19_B109") (pintype "passive"))
    )
    (net (code "235") (name "unconnected-(U18B-Opto_Input20-PadB113)") (class "Default")
      (node (ref "U18") (pin "B113") (pinfunction "Opto_Input20_B113") (pintype "passive"))
    )
    (net (code "236") (name "unconnected-(U18B-Opto_Input21-PadB115)") (class "Default")
      (node (ref "U18") (pin "B115") (pinfunction "Opto_Input21_B115") (pintype "passive"))
    )
    (net (code "237") (name "unconnected-(U18B-Opto_Input22-PadB117)") (class "Default")
      (node (ref "U18") (pin "B117") (pinfunction "Opto_Input22_B117") (pintype "passive"))
    )
    (net (code "238") (name "unconnected-(U18B-Opto_Input23-PadB119)") (class "Default")
      (node (ref "U18") (pin "B119") (pinfunction "Opto_Input23_B119") (pintype "passive"))
    )
    (net (code "239") (name "unconnected-(U18B-Opto_Input_Com1-PadB71)") (class "Default")
      (node (ref "U18") (pin "B71") (pinfunction "Opto_Input_Com1_B71") (pintype "passive"))
    )
    (net (code "240") (name "unconnected-(U18B-Opto_Input_Com2-PadB81)") (class "Default")
      (node (ref "U18") (pin "B81") (pinfunction "Opto_Input_Com2_B81") (pintype "passive"))
    )
    (net (code "241") (name "unconnected-(U18B-Opto_Input_Com3-PadB91)") (class "Default")
      (node (ref "U18") (pin "B91") (pinfunction "Opto_Input_Com3_B91") (pintype "passive"))
    )
    (net (code "242") (name "unconnected-(U18B-Opto_Input_Com4-PadB101)") (class "Default")
      (node (ref "U18") (pin "B101") (pinfunction "Opto_Input_Com4_B101") (pintype "passive"))
    )
    (net (code "243") (name "unconnected-(U18B-Opto_Input_Com5-PadB111)") (class "Default")
      (node (ref "U18") (pin "B111") (pinfunction "Opto_Input_Com5_B111") (pintype "passive"))
    )
    (net (code "244") (name "unconnected-(U18B-PosLimt4-PadB11)") (class "Default")
      (node (ref "U18") (pin "B11") (pinfunction "PosLimt4_B11") (pintype "passive"))
    )
    (net (code "245") (name "unconnected-(U18B-Step4-PadB37)") (class "Default")
      (node (ref "U18") (pin "B37") (pinfunction "Step4_B37") (pintype "passive"))
    )
    (net (code "246") (name "unconnected-(U18B-~Home1-PadB7)") (class "Default")
      (node (ref "U18") (pin "B7") (pinfunction "~Home1_B7") (pintype "passive"))
    )
    (net (code "247") (name "unconnected-(U18B-~Home2-PadB5)") (class "Default")
      (node (ref "U18") (pin "B5") (pinfunction "~Home2_B5") (pintype "passive"))
    )
    (net (code "248") (name "unconnected-(U18B-~Home3-PadB3)") (class "Default")
      (node (ref "U18") (pin "B3") (pinfunction "~Home3_B3") (pintype "passive"))
    )
    (net (code "249") (name "unconnected-(U18B-~Home4-PadB1)") (class "Default")
      (node (ref "U18") (pin "B1") (pinfunction "~Home4_B1") (pintype "passive"))
    )
  )
)
